# DRV8833_Motordrive.net
KiCad netlist of a schematic drawn in Altium Designer
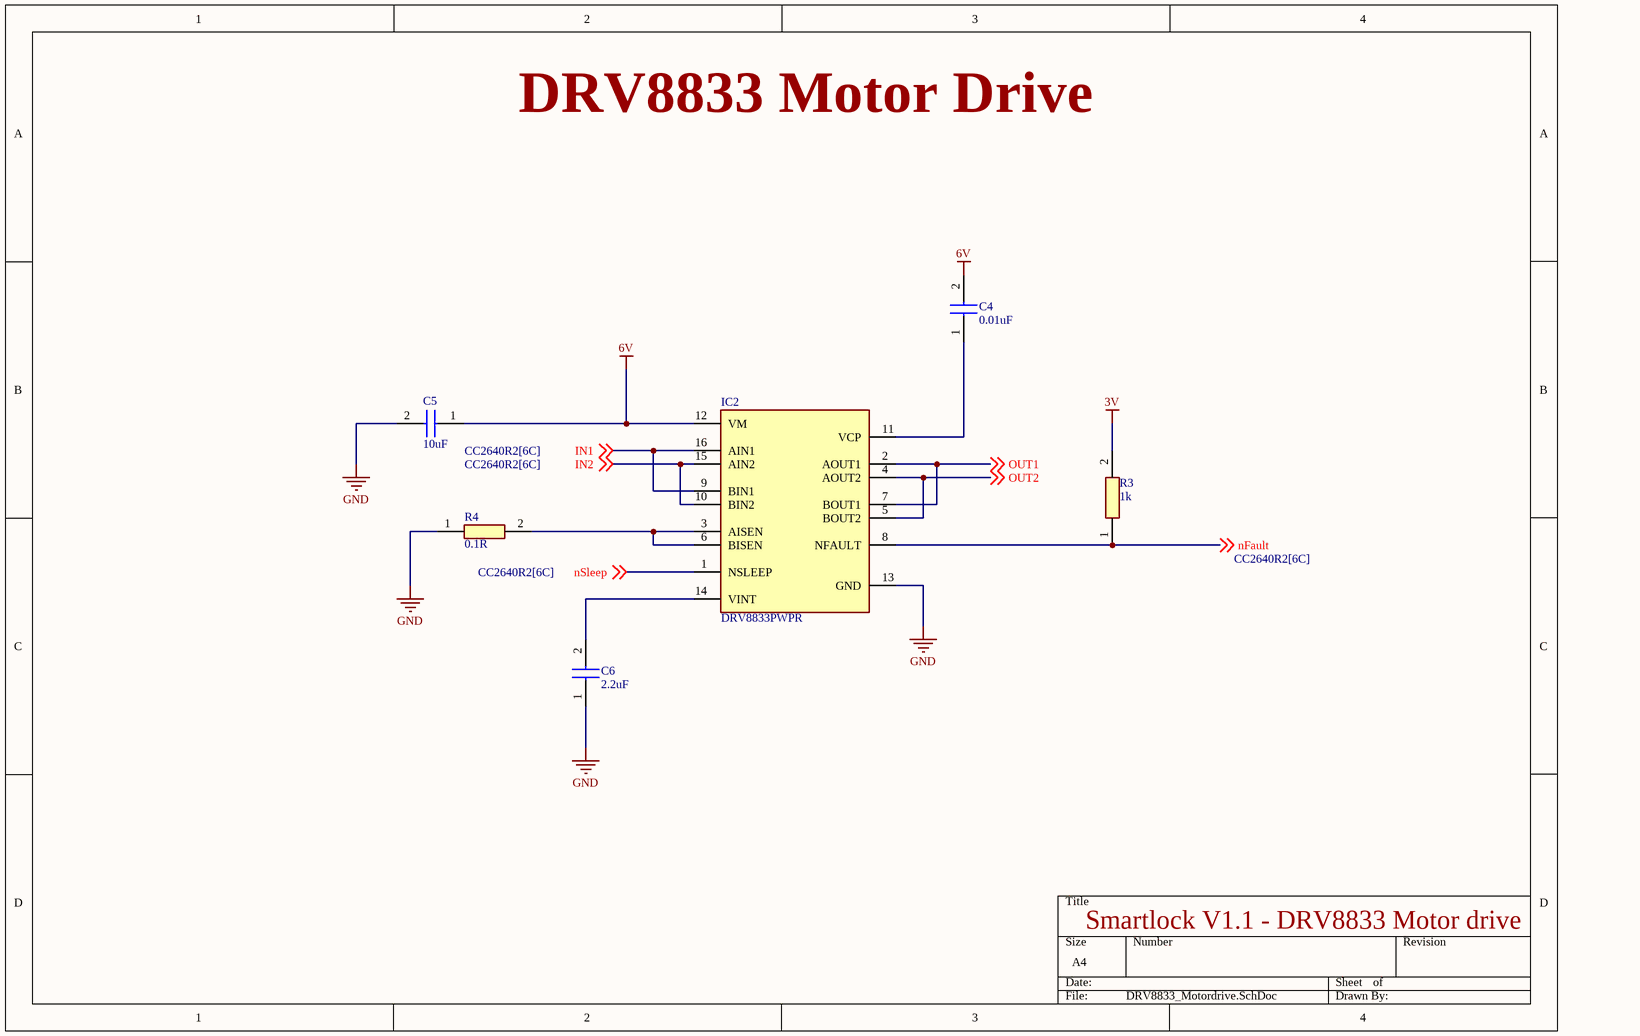
[diagram p0: DRV8833_Motordrive.SchDoc]

(export (version "E")
  (design (tool "Eeschema 10.0.6"))
  (components
    (comp (ref "C4")
      (value "0.01uF")
      (footprint "Smart_lockV1.1:CAPC1005X55N")
      (description "Capacitor,0.01uF")
      (fields
        (field (name "MANUFACTURER_PART_NUMBER") "C1005X7R1C103K050BA")
        (field (name "MOUSER PART NUMBER") "810-C1005X7R1C103K")
      )
      (libsource (lib "*") (part "C1005X7R1C103K050BA"))
    )
    (comp (ref "C5")
      (value "10uF")
      (footprint "Smart_lockV1.1:CAPC2114X145N")
      (description "Capacitor,10uF,16V X7R")
      (fields
        (field (name "MANUFACTURER_PART_NUMBER") "EMK212BB7106MG-T")
        (field (name "MOUSER PART NUMBER") "963-EMK212BB7106MG-T")
      )
      (libsource (lib "*") (part "EMK212BB7106MG-T"))
    )
    (comp (ref "C6")
      (value "2.2uF")
      (footprint "Smart_lockV1.1:C0603")
      (description "Capacitor,2.2uF,X5R,6.3V")
      (fields
        (field (name "MANUFACTURER_PART_NUMBER") "C0603C225K9PACTU")
        (field (name "MOUSER PART NUMBER") "80-C0603C225K9P")
      )
      (libsource (lib "*") (part "C0603C225K9PACTU"))
    )
    (comp (ref "IC2")
      (value "DRV8833PWPR")
      (footprint "SOP65P640X120-16N")
      (description "Integrated Circuit")
      (fields (field (name "MOUSER PART NUMBER") "595-DRV8833PWPR"))
      (libsource (lib "Smart_lockV1.1") (part "DRV8833PWPR"))
    )
    (comp (ref "R3")
      (value "1k")
      (footprint "RESC1608X55N")
      (description "Resistor,1k")
      (fields
        (field (name "MANUFACTURER_PART_NUMBER") "ERJ-3EKF3002V")
        (field (name "MOUSER PART NUMBER") "667-ERJ-3EKF3002V")
      )
      (libsource (lib "Smart_lockV1.1") (part "ERJ-3EKF3002V"))
    )
    (comp (ref "R4")
      (value "0.1R")
      (footprint "Smart_lockV1.1:CSR1206")
      (description "Resistor,0.1R")
      (fields
        (field (name "MANUFACTURER_PART_NUMBER") "CSR1206FKR100")
        (field (name "MOUSER PART NUMBER") "708-CSR1206FKR100")
      )
      (libsource (lib "*") (part "CSR1206FKR100"))
    )
  )
  (nets
    (net (code "1") (name "3V") (class "Default")
      (node (ref "R3") (pin "2") (pinfunction "2_2") (pintype "passive"))
    )
    (net (code "2") (name "6V") (class "Default")
      (node (ref "C4") (pin "2") (pinfunction "2_2") (pintype "passive"))
      (node (ref "C5") (pin "1") (pinfunction "1_1") (pintype "passive"))
      (node (ref "IC2") (pin "12") (pinfunction "VM_12") (pintype "passive"))
    )
    (net (code "3") (name "GND") (class "Default")
      (node (ref "C5") (pin "2") (pinfunction "2_2") (pintype "passive"))
      (node (ref "C6") (pin "1") (pinfunction "1_1") (pintype "passive"))
      (node (ref "IC2") (pin "13") (pinfunction "GND_13") (pintype "passive"))
      (node (ref "R4") (pin "1") (pinfunction "1_1") (pintype "passive"))
    )
    (net (code "4") (name "IN1") (class "Default")
      (node (ref "IC2") (pin "16") (pinfunction "AIN1_16") (pintype "passive"))
      (node (ref "IC2") (pin "9") (pinfunction "BIN1_9") (pintype "passive"))
    )
    (net (code "5") (name "IN2") (class "Default")
      (node (ref "IC2") (pin "10") (pinfunction "BIN2_10") (pintype "passive"))
      (node (ref "IC2") (pin "15") (pinfunction "AIN2_15") (pintype "passive"))
    )
    (net (code "6") (name "Net-(IC2-AISEN)") (class "Default")
      (node (ref "IC2") (pin "3") (pinfunction "AISEN_3") (pintype "passive"))
      (node (ref "IC2") (pin "6") (pinfunction "BISEN_6") (pintype "passive"))
      (node (ref "R4") (pin "2") (pinfunction "2_2") (pintype "passive"))
    )
    (net (code "7") (name "Net-(IC2-VCP)") (class "Default")
      (node (ref "C4") (pin "1") (pinfunction "1_1") (pintype "passive"))
      (node (ref "IC2") (pin "11") (pinfunction "VCP_11") (pintype "passive"))
    )
    (net (code "8") (name "Net-(IC2-VINT)") (class "Default")
      (node (ref "C6") (pin "2") (pinfunction "2_2") (pintype "passive"))
      (node (ref "IC2") (pin "14") (pinfunction "VINT_14") (pintype "passive"))
    )
    (net (code "9") (name "OUT1") (class "Default")
      (node (ref "IC2") (pin "2") (pinfunction "AOUT1_2") (pintype "passive"))
      (node (ref "IC2") (pin "7") (pinfunction "BOUT1_7") (pintype "passive"))
    )
    (net (code "10") (name "OUT2") (class "Default")
      (node (ref "IC2") (pin "4") (pinfunction "AOUT2_4") (pintype "passive"))
      (node (ref "IC2") (pin "5") (pinfunction "BOUT2_5") (pintype "passive"))
    )
    (net (code "11") (name "nFault") (class "Default")
      (node (ref "IC2") (pin "8") (pinfunction "NFAULT_8") (pintype "passive"))
      (node (ref "R3") (pin "1") (pinfunction "1_1") (pintype "passive"))
    )
    (net (code "12") (name "nSleep") (class "Default")
      (node (ref "IC2") (pin "1") (pinfunction "NSLEEP_1") (pintype "passive"))
    )
  )
)
